# ch2.net
KiCad netlist of a schematic drawn in EAGLE
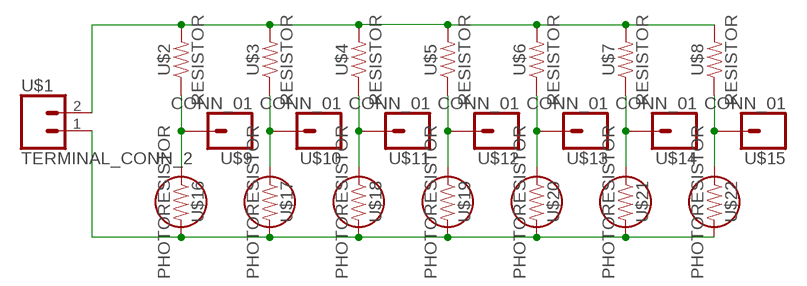
[diagram p0: schematic, sheet 1]

(export (version "E")
  (design (tool "Eeschema 10.0.6"))
  (components
    (comp (ref "U$1")
      (value "TERMINAL_CONN_2")
      (footprint "eagle-import:TERMINAL_CONN_2")
      (libsource (lib "eagle-import") (part "TERMINAL_CONN_2"))
    )
    (comp (ref "U$2")
      (value "RESISTOR")
      (footprint "eagle-import:RESISTOR")
      (libsource (lib "eagle-import") (part "RESISTOR"))
    )
    (comp (ref "U$3")
      (value "RESISTOR")
      (footprint "eagle-import:RESISTOR")
      (libsource (lib "eagle-import") (part "RESISTOR"))
    )
    (comp (ref "U$4")
      (value "RESISTOR")
      (footprint "eagle-import:RESISTOR")
      (libsource (lib "eagle-import") (part "RESISTOR"))
    )
    (comp (ref "U$5")
      (value "RESISTOR")
      (footprint "eagle-import:RESISTOR")
      (libsource (lib "eagle-import") (part "RESISTOR"))
    )
    (comp (ref "U$6")
      (value "RESISTOR")
      (footprint "eagle-import:RESISTOR")
      (libsource (lib "eagle-import") (part "RESISTOR"))
    )
    (comp (ref "U$7")
      (value "RESISTOR")
      (footprint "eagle-import:RESISTOR")
      (libsource (lib "eagle-import") (part "RESISTOR"))
    )
    (comp (ref "U$8")
      (value "RESISTOR")
      (footprint "eagle-import:RESISTOR")
      (libsource (lib "eagle-import") (part "RESISTOR"))
    )
    (comp (ref "U$9")
      (value "CONN_01")
      (footprint "eagle-import:1X01")
      (libsource (lib "eagle-import") (part "CONN_01"))
    )
    (comp (ref "U$10")
      (value "CONN_01")
      (footprint "eagle-import:1X01")
      (libsource (lib "eagle-import") (part "CONN_01"))
    )
    (comp (ref "U$11")
      (value "CONN_01")
      (footprint "eagle-import:1X01")
      (libsource (lib "eagle-import") (part "CONN_01"))
    )
    (comp (ref "U$12")
      (value "CONN_01")
      (footprint "eagle-import:1X01")
      (libsource (lib "eagle-import") (part "CONN_01"))
    )
    (comp (ref "U$13")
      (value "CONN_01")
      (footprint "eagle-import:1X01")
      (libsource (lib "eagle-import") (part "CONN_01"))
    )
    (comp (ref "U$14")
      (value "CONN_01")
      (footprint "eagle-import:1X01")
      (libsource (lib "eagle-import") (part "CONN_01"))
    )
    (comp (ref "U$15")
      (value "CONN_01")
      (footprint "eagle-import:1X01")
      (libsource (lib "eagle-import") (part "CONN_01"))
    )
    (comp (ref "U$16")
      (value "PHOTORESISTOR")
      (footprint "eagle-import:PHOTORESISTOR")
      (libsource (lib "eagle-import") (part "PHOTORESISTOR"))
    )
    (comp (ref "U$17")
      (value "PHOTORESISTOR")
      (footprint "eagle-import:PHOTORESISTOR")
      (libsource (lib "eagle-import") (part "PHOTORESISTOR"))
    )
    (comp (ref "U$18")
      (value "PHOTORESISTOR")
      (footprint "eagle-import:PHOTORESISTOR")
      (libsource (lib "eagle-import") (part "PHOTORESISTOR"))
    )
    (comp (ref "U$19")
      (value "PHOTORESISTOR")
      (footprint "eagle-import:PHOTORESISTOR")
      (libsource (lib "eagle-import") (part "PHOTORESISTOR"))
    )
    (comp (ref "U$20")
      (value "PHOTORESISTOR")
      (footprint "eagle-import:PHOTORESISTOR")
      (libsource (lib "eagle-import") (part "PHOTORESISTOR"))
    )
    (comp (ref "U$21")
      (value "PHOTORESISTOR")
      (footprint "eagle-import:PHOTORESISTOR")
      (libsource (lib "eagle-import") (part "PHOTORESISTOR"))
    )
    (comp (ref "U$22")
      (value "PHOTORESISTOR")
      (footprint "eagle-import:PHOTORESISTOR")
      (libsource (lib "eagle-import") (part "PHOTORESISTOR"))
    )
  )
  (nets
    (net (code "1") (name "Net-(U$1-Pad2)") (class "Default")
      (node (ref "U$1") (pin "2") (pinfunction "2_2") (pintype "passive"))
      (node (ref "U$2") (pin "2") (pinfunction "2_2") (pintype "passive"))
      (node (ref "U$3") (pin "2") (pinfunction "2_2") (pintype "passive"))
      (node (ref "U$4") (pin "2") (pinfunction "2_2") (pintype "passive"))
      (node (ref "U$5") (pin "2") (pinfunction "2_2") (pintype "passive"))
      (node (ref "U$6") (pin "2") (pinfunction "2_2") (pintype "passive"))
      (node (ref "U$7") (pin "2") (pinfunction "2_2") (pintype "passive"))
      (node (ref "U$8") (pin "2") (pinfunction "2_2") (pintype "passive"))
    )
    (net (code "2") (name "Net-(U$16-1)") (class "Default")
      (node (ref "U$16") (pin "P$1") (pinfunction "1_P$1") (pintype "passive"))
      (node (ref "U$2") (pin "1") (pinfunction "1_1") (pintype "passive"))
      (node (ref "U$9") (pin "1") (pinfunction "1_1") (pintype "passive"))
    )
    (net (code "3") (name "Net-(U$16-2)") (class "Default")
      (node (ref "U$1") (pin "1") (pinfunction "1_1") (pintype "passive"))
      (node (ref "U$16") (pin "P$2") (pinfunction "2_P$2") (pintype "passive"))
      (node (ref "U$17") (pin "P$2") (pinfunction "2_P$2") (pintype "passive"))
      (node (ref "U$18") (pin "P$2") (pinfunction "2_P$2") (pintype "passive"))
      (node (ref "U$19") (pin "P$2") (pinfunction "2_P$2") (pintype "passive"))
      (node (ref "U$20") (pin "P$2") (pinfunction "2_P$2") (pintype "passive"))
      (node (ref "U$21") (pin "P$2") (pinfunction "2_P$2") (pintype "passive"))
      (node (ref "U$22") (pin "P$2") (pinfunction "2_P$2") (pintype "passive"))
    )
    (net (code "4") (name "Net-(U$17-1)") (class "Default")
      (node (ref "U$10") (pin "1") (pinfunction "1_1") (pintype "passive"))
      (node (ref "U$17") (pin "P$1") (pinfunction "1_P$1") (pintype "passive"))
      (node (ref "U$3") (pin "1") (pinfunction "1_1") (pintype "passive"))
    )
    (net (code "5") (name "Net-(U$18-1)") (class "Default")
      (node (ref "U$11") (pin "1") (pinfunction "1_1") (pintype "passive"))
      (node (ref "U$18") (pin "P$1") (pinfunction "1_P$1") (pintype "passive"))
      (node (ref "U$4") (pin "1") (pinfunction "1_1") (pintype "passive"))
    )
    (net (code "6") (name "Net-(U$19-1)") (class "Default")
      (node (ref "U$12") (pin "1") (pinfunction "1_1") (pintype "passive"))
      (node (ref "U$19") (pin "P$1") (pinfunction "1_P$1") (pintype "passive"))
      (node (ref "U$5") (pin "1") (pinfunction "1_1") (pintype "passive"))
    )
    (net (code "7") (name "Net-(U$20-1)") (class "Default")
      (node (ref "U$13") (pin "1") (pinfunction "1_1") (pintype "passive"))
      (node (ref "U$20") (pin "P$1") (pinfunction "1_P$1") (pintype "passive"))
      (node (ref "U$6") (pin "1") (pinfunction "1_1") (pintype "passive"))
    )
    (net (code "8") (name "Net-(U$21-1)") (class "Default")
      (node (ref "U$14") (pin "1") (pinfunction "1_1") (pintype "passive"))
      (node (ref "U$21") (pin "P$1") (pinfunction "1_P$1") (pintype "passive"))
      (node (ref "U$7") (pin "1") (pinfunction "1_1") (pintype "passive"))
    )
    (net (code "9") (name "Net-(U$22-1)") (class "Default")
      (node (ref "U$15") (pin "1") (pinfunction "1_1") (pintype "passive"))
      (node (ref "U$22") (pin "P$1") (pinfunction "1_P$1") (pintype "passive"))
      (node (ref "U$8") (pin "1") (pinfunction "1_1") (pintype "passive"))
    )
  )
)
